# POWER_MOD.net
KiCad netlist of a schematic drawn in Altium Designer
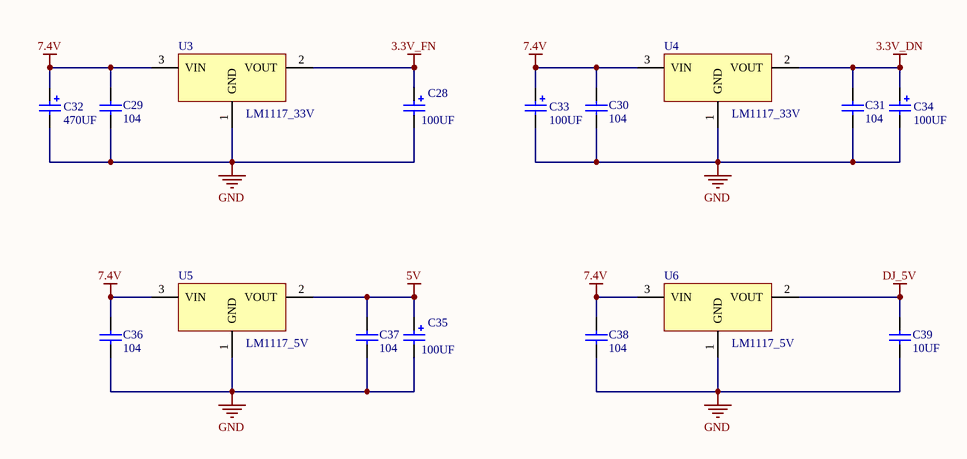
[diagram p0: POWER_MOD.SchDoc]

(export (version "E")
  (design (tool "Eeschema 10.0.6"))
  (components
    (comp (ref "C28") (value "100UF") (footprint "7343") (libsource (lib "飞思卡尔") (part "Cap Pol1")))
    (comp (ref "C29") (value "104") (footprint "0805") (libsource (lib "飞思卡尔") (part "Cap")))
    (comp (ref "C30") (value "104") (footprint "0805") (libsource (lib "飞思卡尔") (part "Cap")))
    (comp (ref "C31") (value "104") (footprint "0805") (libsource (lib "飞思卡尔") (part "Cap")))
    (comp (ref "C32")
      (value "470UF")
      (footprint "tie pian 470uf 10*10.3")
      (libsource (lib "飞思卡尔") (part "Cap Pol1"))
    )
    (comp (ref "C33")
      (value "100UF")
      (footprint "tiepian 100uf 6*7")
      (libsource (lib "飞思卡尔") (part "Cap Pol1"))
    )
    (comp (ref "C34")
      (value "100UF")
      (footprint "tiepian 100uf 6*7")
      (libsource (lib "飞思卡尔") (part "Cap Pol1"))
    )
    (comp (ref "C35")
      (value "100UF")
      (footprint "tiepian 100uf 6*7")
      (libsource (lib "飞思卡尔") (part "Cap Pol1"))
    )
    (comp (ref "C36") (value "104") (footprint "0805") (libsource (lib "飞思卡尔") (part "Cap")))
    (comp (ref "C37") (value "104") (footprint "0805") (libsource (lib "飞思卡尔") (part "Cap")))
    (comp (ref "C38") (value "104") (footprint "0805") (libsource (lib "飞思卡尔") (part "Cap")))
    (comp (ref "C39") (value "10UF") (footprint "1206") (libsource (lib "飞思卡尔") (part "Cap")))
    (comp (ref "U3") (value "LM1117_33V") (footprint "SOT-223") (libsource (lib "飞思卡尔") (part "LM1117_5V")))
    (comp (ref "U4") (value "LM1117_33V") (footprint "SOT-223") (libsource (lib "飞思卡尔") (part "LM1117_5V")))
    (comp (ref "U5") (value "LM1117_5V") (footprint "SOT-223") (libsource (lib "飞思卡尔") (part "LM1117_5V")))
    (comp (ref "U6") (value "LM1117_5V") (footprint "SOT-223") (libsource (lib "飞思卡尔") (part "LM1117_5V")))
  )
  (nets
    (net (code "1") (name "3.3V_DN") (class "Default")
      (node (ref "C31") (pin "1") (pinfunction "1_1") (pintype "passive"))
      (node (ref "C34") (pin "1") (pinfunction "1_1") (pintype "passive"))
      (node (ref "U4") (pin "2") (pinfunction "VOUT_2") (pintype "passive"))
    )
    (net (code "2") (name "3.3V_FN") (class "Default")
      (node (ref "C28") (pin "1") (pinfunction "1_1") (pintype "passive"))
      (node (ref "U3") (pin "2") (pinfunction "VOUT_2") (pintype "passive"))
    )
    (net (code "3") (name "5V") (class "Default")
      (node (ref "C35") (pin "1") (pinfunction "1_1") (pintype "passive"))
      (node (ref "C37") (pin "1") (pinfunction "1_1") (pintype "passive"))
      (node (ref "U5") (pin "2") (pinfunction "VOUT_2") (pintype "passive"))
    )
    (net (code "4") (name "7.4V") (class "Default")
      (node (ref "C29") (pin "1") (pinfunction "1_1") (pintype "passive"))
      (node (ref "C30") (pin "1") (pinfunction "1_1") (pintype "passive"))
      (node (ref "C32") (pin "1") (pinfunction "1_1") (pintype "passive"))
      (node (ref "C33") (pin "1") (pinfunction "1_1") (pintype "passive"))
      (node (ref "C36") (pin "1") (pinfunction "1_1") (pintype "passive"))
      (node (ref "C38") (pin "1") (pinfunction "1_1") (pintype "passive"))
      (node (ref "U3") (pin "3") (pinfunction "VIN_3") (pintype "passive"))
      (node (ref "U4") (pin "3") (pinfunction "VIN_3") (pintype "passive"))
      (node (ref "U5") (pin "3") (pinfunction "VIN_3") (pintype "passive"))
      (node (ref "U6") (pin "3") (pinfunction "VIN_3") (pintype "passive"))
    )
    (net (code "5") (name "DJ_5V") (class "Default")
      (node (ref "C39") (pin "1") (pinfunction "1_1") (pintype "passive"))
      (node (ref "U6") (pin "2") (pinfunction "VOUT_2") (pintype "passive"))
    )
    (net (code "6") (name "GND") (class "Default")
      (node (ref "C28") (pin "2") (pinfunction "2_2") (pintype "passive"))
      (node (ref "C29") (pin "2") (pinfunction "2_2") (pintype "passive"))
      (node (ref "C30") (pin "2") (pinfunction "2_2") (pintype "passive"))
      (node (ref "C31") (pin "2") (pinfunction "2_2") (pintype "passive"))
      (node (ref "C32") (pin "2") (pinfunction "2_2") (pintype "passive"))
      (node (ref "C33") (pin "2") (pinfunction "2_2") (pintype "passive"))
      (node (ref "C34") (pin "2") (pinfunction "2_2") (pintype "passive"))
      (node (ref "C35") (pin "2") (pinfunction "2_2") (pintype "passive"))
      (node (ref "C36") (pin "2") (pinfunction "2_2") (pintype "passive"))
      (node (ref "C37") (pin "2") (pinfunction "2_2") (pintype "passive"))
      (node (ref "C38") (pin "2") (pinfunction "2_2") (pintype "passive"))
      (node (ref "C39") (pin "2") (pinfunction "2_2") (pintype "passive"))
      (node (ref "U3") (pin "1") (pinfunction "GND_1") (pintype "passive"))
      (node (ref "U4") (pin "1") (pinfunction "GND_1") (pintype "passive"))
      (node (ref "U5") (pin "1") (pinfunction "GND_1") (pintype "passive"))
      (node (ref "U6") (pin "1") (pinfunction "GND_1") (pintype "passive"))
    )
  )
)
